# Buck2.net
KiCad netlist of a schematic drawn in Altium Designer
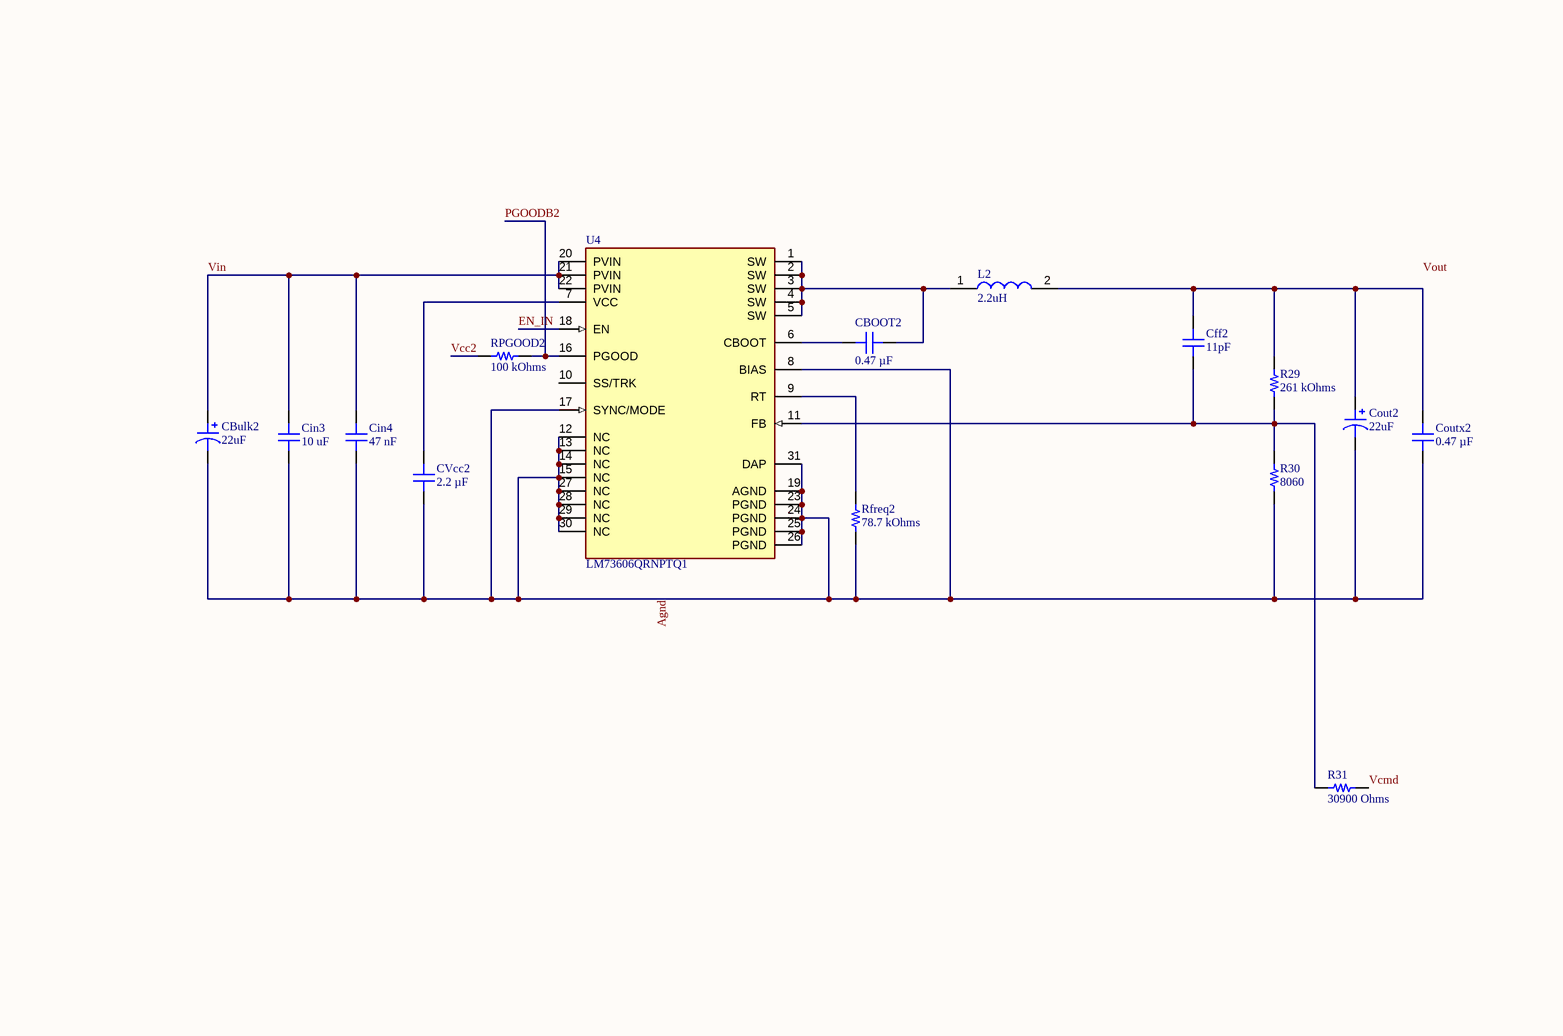
[diagram p0: Buck2.SchDoc]

(export (version "E")
  (design (tool "Eeschema 10.0.6"))
  (components
    (comp (ref "CBOOT2")
      (value "0.47 µF")
      (footprint "CAP 0603_1608")
      (description "CAP CER 0.47UF 50V X5R 0603")
      (fields
        (field (name "PART NUMBER") "CL10A474KB8NNNC")
        (field (name "MANUFACTURER") "Samsung Electro-Mechanics")
      )
      (libsource (lib "Celestial Altium Library - altium_library") (part "Capacitor"))
    )
    (comp (ref "CBulk2")
      (value "22uF")
      (footprint "CAP ALSMD 8.3MM H10.5MM")
      (description "CAP ALUM 68UF 20% 63V SMD")
      (fields
        (field (name "PART NUMBER") "EEE-FK1J680UP")
        (field (name "MANUFACTURER") "Panasonic Electronic Components")
      )
      (libsource (lib "Celestial Altium Library - altium_library") (part "Polarised Capacitor"))
    )
    (comp (ref "Cff2")
      (value "11pF")
      (footprint "CAP 0603_1608")
      (description "CAP CER 1UF 16V X7R 0603")
      (fields (field (name "PART NUMBER") "C0603C105K4RACAUTO") (field (name "MANUFACTURER") "KEMET"))
      (libsource (lib "Celestial Altium Library - altium_library") (part "Capacitor"))
    )
    (comp (ref "Cin3")
      (value "10 uF")
      (footprint "CAP 0603_1608")
      (description "CAP CER 0.10UF 50V X7R 0603")
      (fields (field (name "PART NUMBER") "C0603C104K5RECAUTO") (field (name "MANUFACTURER") "KEMET"))
      (libsource (lib "Celestial Altium Library - altium_library") (part "Capacitor"))
    )
    (comp (ref "Cin4")
      (value "47 nF")
      (footprint "CAP 0603_1608")
      (description "CAP CER 0.10UF 50V X7R 0603")
      (fields (field (name "PART NUMBER") "C0603C104K5RECAUTO") (field (name "MANUFACTURER") "KEMET"))
      (libsource (lib "Celestial Altium Library - altium_library") (part "Capacitor"))
    )
    (comp (ref "Cout2")
      (value "22uF")
      (footprint "CAP ALSMD 8.3MM H10.5MM")
      (description "CAP ALUM 68UF 20% 63V SMD")
      (fields
        (field (name "PART NUMBER") "EEE-FK1J680UP")
        (field (name "MANUFACTURER") "Panasonic Electronic Components")
      )
      (libsource (lib "Celestial Altium Library - altium_library") (part "Polarised Capacitor"))
    )
    (comp (ref "Coutx2")
      (value "0.47 µF")
      (footprint "CAP 0603_1608")
      (description "CAP CER 0.47UF 50V X5R 0603")
      (fields
        (field (name "PART NUMBER") "CL10A474KB8NNNC")
        (field (name "MANUFACTURER") "Samsung Electro-Mechanics")
      )
      (libsource (lib "Celestial Altium Library - altium_library") (part "Capacitor"))
    )
    (comp (ref "CVcc2")
      (value "2.2 µF")
      (footprint "CAP 0603_1608")
      (description "CAP CER 2.2UF 10V X7R 0603")
      (fields
        (field (name "PART NUMBER") "CL10B225KP8NFNC")
        (field (name "MANUFACTURER") "Samsung Electro-Mechanics")
      )
      (libsource (lib "Celestial Altium Library - altium_library") (part "Capacitor"))
    )
    (comp (ref "L2")
      (value "2.2uH")
      (footprint "SamacSys:INDPM104104X480N")
      (description "Inductor")
      (fields
        (field (name "MANUFACTURER_PART_NUMBER") "B82464P4334M000")
        (field (name "MOUSER PART NUMBER") "871-B82464P4334M")
      )
      (libsource (lib "*") (part "B82464P4334M000"))
    )
    (comp (ref "R29")
      (value "261 kOhms")
      (footprint "RES 0603_1608")
      (description "RES SMD 100K OHM 0.1% 1/16W 0603")
      (fields
        (field (name "PART NUMBER") "CPF0603B100KE")
        (field (name "MANUFACTURER") "TE Connectivity Passive Product")
      )
      (libsource (lib "Celestial Altium Library - altium_library") (part "Resistor"))
    )
    (comp (ref "R30")
      (value "8060")
      (footprint "RES 0603_1608")
      (description "RES SMD 100K OHM 0.1% 1/16W 0603")
      (fields
        (field (name "PART NUMBER") "CPF0603B100KE")
        (field (name "MANUFACTURER") "TE Connectivity Passive Product")
      )
      (libsource (lib "Celestial Altium Library - altium_library") (part "Resistor"))
    )
    (comp (ref "R31")
      (value "30900 Ohms")
      (footprint "RES 0603_1608")
      (description "RES SMD 100K OHM 0.1% 1/16W 0603")
      (fields
        (field (name "PART NUMBER") "CPF0603B100KE")
        (field (name "MANUFACTURER") "TE Connectivity Passive Product")
      )
      (libsource (lib "Celestial Altium Library - altium_library") (part "Resistor"))
    )
    (comp (ref "Rfreq2")
      (value "78.7 kOhms")
      (footprint "RES 0603_1608")
      (description "RES SMD 78.7K OHM 1% 1/16W 0603")
      (fields
        (field (name "PART NUMBER") "CPF0603F78K7C1")
        (field (name "MANUFACTURER") "TE Connectivity Passive Product")
      )
      (libsource (lib "Celestial Altium Library - altium_library") (part "Resistor"))
    )
    (comp (ref "RPGOOD2")
      (value "100 kOhms")
      (footprint "RES 0603_1608")
      (description "RES SMD 100K OHM 0.1% 1/16W 0603")
      (fields
        (field (name "PART NUMBER") "CPF0603B100KE")
        (field (name "MANUFACTURER") "TE Connectivity Passive Product")
      )
      (libsource (lib "Celestial Altium Library - altium_library") (part "Resistor"))
    )
    (comp (ref "U4")
      (value "LM73606QRNPTQ1")
      (footprint "FP-RNP0030A-IPC_C")
      (description "IC REG BUCK ADJUSTABLE 6A 30WQFN")
      (fields
        (field (name "OCTOPART") "https://octopart.com/lm73606qrnptq1-texas+instruments-87960447")
        (field (name "MANUFACTURER") "Texas Instruments")
      )
      (libsource (lib "Components - 06.07.23 - 15.31") (part "CMP-04918-000121-1"))
    )
  )
  (nets
    (net (code "1") (name "/Agnd") (class "Default")
      (node (ref "CBulk2") (pin "2") (pinfunction "2_2") (pintype "passive"))
      (node (ref "CVcc2") (pin "1") (pinfunction "1_1") (pintype "passive"))
      (node (ref "Cin3") (pin "1") (pinfunction "1_1") (pintype "passive"))
      (node (ref "Cin4") (pin "1") (pinfunction "1_1") (pintype "passive"))
      (node (ref "Cout2") (pin "2") (pinfunction "2_2") (pintype "passive"))
      (node (ref "Coutx2") (pin "1") (pinfunction "1_1") (pintype "passive"))
      (node (ref "R30") (pin "1") (pinfunction "1_1") (pintype "passive"))
      (node (ref "Rfreq2") (pin "1") (pinfunction "1_1") (pintype "passive"))
      (node (ref "U4") (pin "12") (pinfunction "NC_12") (pintype "passive"))
      (node (ref "U4") (pin "13") (pinfunction "NC_13") (pintype "passive"))
      (node (ref "U4") (pin "14") (pinfunction "NC_14") (pintype "passive"))
      (node (ref "U4") (pin "15") (pinfunction "NC_15") (pintype "passive"))
      (node (ref "U4") (pin "17") (pinfunction "SYNC/MODE_17") (pintype "input"))
      (node (ref "U4") (pin "19") (pinfunction "AGND_19") (pintype "power_in"))
      (node (ref "U4") (pin "23") (pinfunction "PGND_23") (pintype "power_in"))
      (node (ref "U4") (pin "24") (pinfunction "PGND_24") (pintype "power_in"))
      (node (ref "U4") (pin "25") (pinfunction "PGND_25") (pintype "power_in"))
      (node (ref "U4") (pin "26") (pinfunction "PGND_26") (pintype "power_in"))
      (node (ref "U4") (pin "27") (pinfunction "NC_27") (pintype "passive"))
      (node (ref "U4") (pin "28") (pinfunction "NC_28") (pintype "passive"))
      (node (ref "U4") (pin "29") (pinfunction "NC_29") (pintype "passive"))
      (node (ref "U4") (pin "30") (pinfunction "NC_30") (pintype "passive"))
      (node (ref "U4") (pin "31") (pinfunction "DAP_31") (pintype "power_in"))
      (node (ref "U4") (pin "8") (pinfunction "BIAS_8") (pintype "power_in"))
    )
    (net (code "2") (name "/EN_IN") (class "Default")
      (node (ref "U4") (pin "18") (pinfunction "EN_18") (pintype "input"))
    )
    (net (code "3") (name "/PGOODB2") (class "Default")
      (node (ref "RPGOOD2") (pin "1") (pinfunction "1_1") (pintype "passive"))
      (node (ref "U4") (pin "16") (pinfunction "PGOOD_16") (pintype "open_collector"))
    )
    (net (code "4") (name "/Vcc2") (class "Default")
      (node (ref "RPGOOD2") (pin "2") (pinfunction "2_2") (pintype "passive"))
    )
    (net (code "5") (name "/Vcmd") (class "Default")
      (node (ref "R31") (pin "1") (pinfunction "1_1") (pintype "passive"))
    )
    (net (code "6") (name "/Vin") (class "Default")
      (node (ref "CBulk2") (pin "1") (pinfunction "1_1") (pintype "passive"))
      (node (ref "Cin3") (pin "2") (pinfunction "2_2") (pintype "passive"))
      (node (ref "Cin4") (pin "2") (pinfunction "2_2") (pintype "passive"))
      (node (ref "U4") (pin "20") (pinfunction "PVIN_20") (pintype "power_in"))
      (node (ref "U4") (pin "21") (pinfunction "PVIN_21") (pintype "power_in"))
      (node (ref "U4") (pin "22") (pinfunction "PVIN_22") (pintype "power_in"))
    )
    (net (code "8") (name "Net-(CBOOT2-Pad2)") (class "Default")
      (node (ref "CBOOT2") (pin "2") (pinfunction "2_2") (pintype "passive"))
      (node (ref "L2") (pin "1") (pinfunction "1_1") (pintype "passive"))
      (node (ref "U4") (pin "1") (pinfunction "SW_1") (pintype "passive"))
      (node (ref "U4") (pin "2") (pinfunction "SW_2") (pintype "passive"))
      (node (ref "U4") (pin "3") (pinfunction "SW_3") (pintype "passive"))
      (node (ref "U4") (pin "4") (pinfunction "SW_4") (pintype "passive"))
      (node (ref "U4") (pin "5") (pinfunction "SW_5") (pintype "passive"))
    )
    (net (code "9") (name "Net-(Cff2-Pad2)") (class "Default")
      (node (ref "Cff2") (pin "2") (pinfunction "2_2") (pintype "passive"))
      (node (ref "Cout2") (pin "1") (pinfunction "1_1") (pintype "passive"))
      (node (ref "Coutx2") (pin "2") (pinfunction "2_2") (pintype "passive"))
      (node (ref "L2") (pin "2") (pinfunction "2_2") (pintype "passive"))
      (node (ref "R29") (pin "2") (pinfunction "2_2") (pintype "passive"))
    )
    (net (code "10") (name "Net-(U4-CBOOT)") (class "Default")
      (node (ref "CBOOT2") (pin "1") (pinfunction "1_1") (pintype "passive"))
      (node (ref "U4") (pin "6") (pinfunction "CBOOT_6") (pintype "passive"))
    )
    (net (code "11") (name "Net-(U4-FB)") (class "Default")
      (node (ref "Cff2") (pin "1") (pinfunction "1_1") (pintype "passive"))
      (node (ref "R29") (pin "1") (pinfunction "1_1") (pintype "passive"))
      (node (ref "R30") (pin "2") (pinfunction "2_2") (pintype "passive"))
      (node (ref "R31") (pin "2") (pinfunction "2_2") (pintype "passive"))
      (node (ref "U4") (pin "11") (pinfunction "FB_11") (pintype "input"))
    )
    (net (code "12") (name "Net-(U4-RT)") (class "Default")
      (node (ref "Rfreq2") (pin "2") (pinfunction "2_2") (pintype "passive"))
      (node (ref "U4") (pin "9") (pinfunction "RT_9") (pintype "passive"))
    )
    (net (code "13") (name "Net-(U4-VCC)") (class "Default")
      (node (ref "CVcc2") (pin "2") (pinfunction "2_2") (pintype "passive"))
      (node (ref "U4") (pin "7") (pinfunction "VCC_7") (pintype "power_in"))
    )
    (net (code "14") (name "unconnected-(U4-SS{slash}TRK-Pad10)") (class "Default")
      (node (ref "U4") (pin "10") (pinfunction "SS/TRK_10") (pintype "passive"))
    )
  )
)
